# LCL_sch.net
KiCad netlist of a schematic drawn in Altium Designer
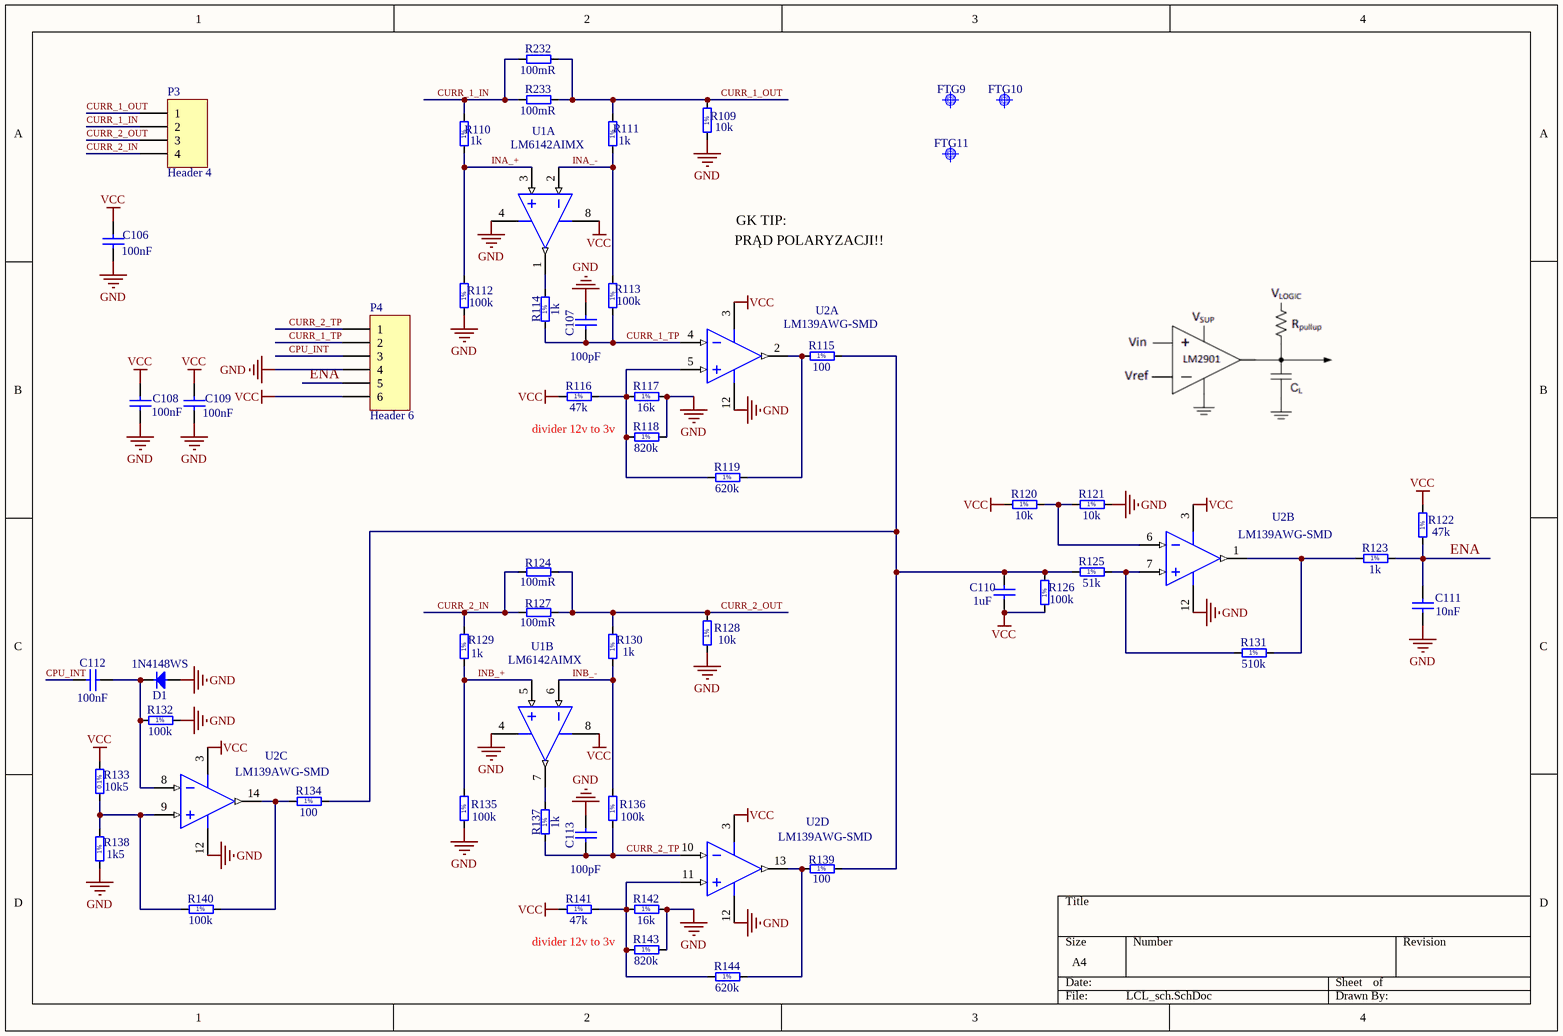
[diagram p0: LCL_sch.SchDoc]

(export (version "E")
  (design (tool "Eeschema 10.0.6"))
  (components
    (comp (ref "C106")
      (value "100nF")
      (footprint "CAPC1608X87N")
      (description "Non-polarised capacitor")
      (fields
        (field (name "PART NUMBER") "CC0603_100NF_50V_10%_X7R")
        (field (name "VOLTAGE") "50V")
        (field (name "AUTHOR") "CERN DEM JLC")
      )
      (libsource (lib "Capacitors") (part "Capacitor - non polarized"))
    )
    (comp (ref "C107")
      (value "100pF")
      (footprint "CAPC1608X87N")
      (description "Non-polarised capacitor")
      (fields
        (field (name "PART NUMBER") "CC0603_100PF_50V_10%_X7R")
        (field (name "VOLTAGE") "50V")
        (field (name "AUTHOR") "CERN DEM JLC")
      )
      (libsource (lib "Capacitors") (part "Capacitor - non polarized"))
    )
    (comp (ref "C108")
      (value "100nF")
      (footprint "CAPC1608X87N")
      (description "Non-polarised capacitor")
      (fields
        (field (name "PART NUMBER") "CC0603_100NF_50V_10%_X7R")
        (field (name "VOLTAGE") "50V")
        (field (name "AUTHOR") "CERN DEM JLC")
      )
      (libsource (lib "Capacitors") (part "Capacitor - non polarized"))
    )
    (comp (ref "C109")
      (value "100nF")
      (footprint "CAPC1608X87N")
      (description "Non-polarised capacitor")
      (fields
        (field (name "PART NUMBER") "CC0603_100NF_50V_10%_X7R")
        (field (name "VOLTAGE") "50V")
        (field (name "AUTHOR") "CERN DEM JLC")
      )
      (libsource (lib "Capacitors") (part "Capacitor - non polarized"))
    )
    (comp (ref "C110")
      (value "1uF")
      (footprint "CAPC1608X87N")
      (description "Non-polarised capacitor")
      (fields
        (field (name "PART NUMBER") "CC0603_1UF_25V_10%_X7R")
        (field (name "VOLTAGE") "25V")
        (field (name "AUTHOR") "CERN DEM JLC")
      )
      (libsource (lib "Capacitors") (part "Capacitor - non polarized"))
    )
    (comp (ref "C111")
      (value "10nF")
      (footprint "CAPC1608X87N")
      (description "Non-polarised capacitor")
      (fields
        (field (name "PART NUMBER") "CC0603_10NF_50V_10%_X7R")
        (field (name "VOLTAGE") "50V")
        (field (name "AUTHOR") "CERN DEM JLC")
      )
      (libsource (lib "Capacitors") (part "Capacitor - non polarized"))
    )
    (comp (ref "C112")
      (value "100nF")
      (footprint "CAPC1608X87N")
      (description "Non-polarised capacitor")
      (fields
        (field (name "PART NUMBER") "CC0603_100NF_50V_10%_X7R")
        (field (name "VOLTAGE") "50V")
        (field (name "AUTHOR") "CERN DEM JLC")
      )
      (libsource (lib "Capacitors") (part "Capacitor - non polarized"))
    )
    (comp (ref "C113")
      (value "100pF")
      (footprint "CAPC1608X87N")
      (description "Non-polarised capacitor")
      (fields
        (field (name "PART NUMBER") "CC0603_100PF_50V_10%_X7R")
        (field (name "VOLTAGE") "50V")
        (field (name "AUTHOR") "CERN DEM JLC")
      )
      (libsource (lib "Capacitors") (part "Capacitor - non polarized"))
    )
    (comp (ref "D1")
      (value "1N4148WS")
      (footprint "SODFL2512X100N")
      (description "Diode")
      (fields
        (field (name "VOLTAGE") "75V")
        (field (name "POWER") "150mA")
        (field (name "AUTHOR") "CERN DEM JLC")
      )
      (libsource (lib "ICs And Semiconductors") (part "Diode"))
    )
    (comp (ref "FTG9")
      (value "Use only in PCB")
      (footprint "FIDUCIAL_TOP_C100-200")
      (description "Fiducial Target")
      (fields (field (name "PART NUMBER") "FIDUCIAL_TARGET_C100-200") (field (name "AUTHOR") "CERN DEM JLC"))
      (libsource (lib "Eletro-mechanical") (part "Fiducial Target"))
    )
    (comp (ref "FTG10")
      (value "Use only in PCB")
      (footprint "FIDUCIAL_TOP_C100-200")
      (description "Fiducial Target")
      (fields (field (name "PART NUMBER") "FIDUCIAL_TARGET_C100-200") (field (name "AUTHOR") "CERN DEM JLC"))
      (libsource (lib "Eletro-mechanical") (part "Fiducial Target"))
    )
    (comp (ref "FTG11")
      (value "Use only in PCB")
      (footprint "FIDUCIAL_TOP_C100-200")
      (description "Fiducial Target")
      (fields (field (name "PART NUMBER") "FIDUCIAL_TARGET_C100-200") (field (name "AUTHOR") "CERN DEM JLC"))
      (libsource (lib "Eletro-mechanical") (part "Fiducial Target"))
    )
    (comp (ref "P3")
      (value "Header 4")
      (footprint "1x4 Header 2mm male")
      (description "Header, 4-Pin")
      (fields (field (name "PUBLISHER") "Altium Limited"))
      (libsource (lib "Connectors-headers") (part "Header 4"))
    )
    (comp (ref "P4")
      (value "Header 6")
      (footprint "2x3 Header 2mm male")
      (description "Header, 6-Pin")
      (fields (field (name "PUBLISHER") "Altium Limited"))
      (libsource (lib "Connectors-headers") (part "Header 6"))
    )
    (comp (ref "R109")
      (value "10k")
      (footprint "RESC1608X55N")
      (description "Resistor - 1%")
      (fields
        (field (name "PART NUMBER") "R0603_10K_1%_0.1W_100PPM")
        (field (name "POWER") "0.1W")
        (field (name "AUTHOR") "CERN DEM JLC")
      )
      (libsource (lib "Resistors") (part "Resistor - 1%"))
    )
    (comp (ref "R110")
      (value "1k")
      (footprint "RESC1608X55N")
      (description "Resistor - 1%")
      (fields
        (field (name "PART NUMBER") "R0603_1K_1%_0.1W_100PPM")
        (field (name "POWER") "0.1W")
        (field (name "AUTHOR") "CERN DEM JLC")
      )
      (libsource (lib "Resistors") (part "Resistor - 1%"))
    )
    (comp (ref "R111")
      (value "1k")
      (footprint "RESC1608X55N")
      (description "Resistor - 1%")
      (fields
        (field (name "PART NUMBER") "R0603_1K_1%_0.1W_100PPM")
        (field (name "POWER") "0.1W")
        (field (name "AUTHOR") "CERN DEM JLC")
      )
      (libsource (lib "Resistors") (part "Resistor - 1%"))
    )
    (comp (ref "R112")
      (value "100k")
      (footprint "RESC1608X55N")
      (description "Resistor - 1%")
      (fields
        (field (name "PART NUMBER") "R0603_100K_1%_0.1W_100PPM")
        (field (name "POWER") "0.1W")
        (field (name "AUTHOR") "CERN DEM JLC")
      )
      (libsource (lib "Resistors") (part "Resistor - 1%"))
    )
    (comp (ref "R113")
      (value "100k")
      (footprint "RESC1608X55N")
      (description "Resistor - 1%")
      (fields
        (field (name "PART NUMBER") "R0603_100K_1%_0.1W_100PPM")
        (field (name "POWER") "0.1W")
        (field (name "AUTHOR") "CERN DEM JLC")
      )
      (libsource (lib "Resistors") (part "Resistor - 1%"))
    )
    (comp (ref "R114")
      (value "1k")
      (footprint "RESC1608X55N")
      (description "Resistor - 1%")
      (fields
        (field (name "PART NUMBER") "R0603_1K_1%_0.1W_100PPM")
        (field (name "POWER") "0.1W")
        (field (name "AUTHOR") "CERN DEM JLC")
      )
      (libsource (lib "Resistors") (part "Resistor - 1%"))
    )
    (comp (ref "R115")
      (value "100")
      (footprint "RESC1608X55N")
      (description "Resistor - 1%")
      (fields
        (field (name "PART NUMBER") "R0603_100R_1%_0.1W_100PPM")
        (field (name "POWER") "0.1W")
        (field (name "AUTHOR") "CERN DEM JLC")
      )
      (libsource (lib "Resistors") (part "Resistor - 1%"))
    )
    (comp (ref "R116")
      (value "47k")
      (footprint "RESC1608X55N")
      (description "Resistor - 1%")
      (fields
        (field (name "PART NUMBER") "R0603_47K_1%_0.1W_100PPM")
        (field (name "POWER") "0.1W")
        (field (name "AUTHOR") "CERN DEM JLC")
      )
      (libsource (lib "Resistors") (part "Resistor - 1%"))
    )
    (comp (ref "R117")
      (value "16k")
      (footprint "RESC1608X55N")
      (description "Resistor - 1%")
      (fields
        (field (name "PART NUMBER") "R0603_16K_1%_0.1W_100PPM")
        (field (name "POWER") "0.1W")
        (field (name "AUTHOR") "CERN DEM JLC")
      )
      (libsource (lib "Resistors") (part "Resistor - 1%"))
    )
    (comp (ref "R118")
      (value "820k")
      (footprint "RESC1608X55N")
      (description "Resistor - 1%")
      (fields
        (field (name "PART NUMBER") "R0603_820K_1%_0.1W_100PPM")
        (field (name "POWER") "0.1W")
        (field (name "AUTHOR") "CERN DEM JLC")
      )
      (libsource (lib "Resistors") (part "Resistor - 1%"))
    )
    (comp (ref "R119")
      (value "620k")
      (footprint "RESC1608X55N")
      (description "Resistor - 1%")
      (fields
        (field (name "PART NUMBER") "R0603_620K_1%_0.1W_100PPM")
        (field (name "POWER") "0.1W")
        (field (name "AUTHOR") "CERN DEM JLC")
      )
      (libsource (lib "Resistors") (part "Resistor - 1%"))
    )
    (comp (ref "R120")
      (value "10k")
      (footprint "RESC1608X55N")
      (description "Resistor - 1%")
      (fields
        (field (name "PART NUMBER") "R0603_10K_1%_0.1W_100PPM")
        (field (name "POWER") "0.1W")
        (field (name "AUTHOR") "CERN DEM JLC")
      )
      (libsource (lib "Resistors") (part "Resistor - 1%"))
    )
    (comp (ref "R121")
      (value "10k")
      (footprint "RESC1608X55N")
      (description "Resistor - 1%")
      (fields
        (field (name "PART NUMBER") "R0603_10K_1%_0.1W_100PPM")
        (field (name "POWER") "0.1W")
        (field (name "AUTHOR") "CERN DEM JLC")
      )
      (libsource (lib "Resistors") (part "Resistor - 1%"))
    )
    (comp (ref "R122")
      (value "47k")
      (footprint "RESC1608X55N")
      (description "Resistor - 1%")
      (fields
        (field (name "PART NUMBER") "R0603_47K_1%_0.1W_100PPM")
        (field (name "POWER") "0.1W")
        (field (name "AUTHOR") "CERN DEM JLC")
      )
      (libsource (lib "Resistors") (part "Resistor - 1%"))
    )
    (comp (ref "R123")
      (value "1k")
      (footprint "RESC1608X55N")
      (description "Resistor - 1%")
      (fields
        (field (name "PART NUMBER") "R0603_1K_1%_0.1W_100PPM")
        (field (name "POWER") "0.1W")
        (field (name "AUTHOR") "CERN DEM JLC")
      )
      (libsource (lib "Resistors") (part "Resistor - 1%"))
    )
    (comp (ref "R124")
      (value "100mR")
      (footprint "RESC1608X55N")
      (description "Resistor")
      (fields
        (field (name "PART NUMBER") "100mR 0603")
        (field (name "MANUFACTURER") "GENERIC")
        (field (name "AUTHOR") "CERN DEM JLC")
      )
      (libsource (lib "Resistors") (part "Resistor"))
    )
    (comp (ref "R125")
      (value "51k")
      (footprint "RESC1608X55N")
      (description "Resistor - 1%")
      (fields
        (field (name "PART NUMBER") "R0603_51K_1%_0.1W_100PPM")
        (field (name "POWER") "0.1W")
        (field (name "AUTHOR") "CERN DEM JLC")
      )
      (libsource (lib "Resistors") (part "Resistor - 1%"))
    )
    (comp (ref "R126")
      (value "100k")
      (footprint "RESC1608X55N")
      (description "Resistor - 1%")
      (fields
        (field (name "PART NUMBER") "R0603_100K_1%_0.1W_100PPM")
        (field (name "POWER") "0.1W")
        (field (name "AUTHOR") "CERN DEM JLC")
      )
      (libsource (lib "Resistors") (part "Resistor - 1%"))
    )
    (comp (ref "R127")
      (value "100mR")
      (footprint "RESC1608X55N")
      (description "Resistor")
      (fields
        (field (name "PART NUMBER") "100mR 0603")
        (field (name "MANUFACTURER") "GENERIC")
        (field (name "AUTHOR") "CERN DEM JLC")
      )
      (libsource (lib "Resistors") (part "Resistor"))
    )
    (comp (ref "R128")
      (value "10k")
      (footprint "RESC1608X55N")
      (description "Resistor - 1%")
      (fields
        (field (name "PART NUMBER") "R0603_10K_1%_0.1W_100PPM")
        (field (name "POWER") "0.1W")
        (field (name "AUTHOR") "CERN DEM JLC")
      )
      (libsource (lib "Resistors") (part "Resistor - 1%"))
    )
    (comp (ref "R129")
      (value "1k")
      (footprint "RESC1608X55N")
      (description "Resistor - 1%")
      (fields
        (field (name "PART NUMBER") "R0603_1K_1%_0.1W_100PPM")
        (field (name "POWER") "0.1W")
        (field (name "AUTHOR") "CERN DEM JLC")
      )
      (libsource (lib "Resistors") (part "Resistor - 1%"))
    )
    (comp (ref "R130")
      (value "1k")
      (footprint "RESC1608X55N")
      (description "Resistor - 1%")
      (fields
        (field (name "PART NUMBER") "R0603_1K_1%_0.1W_100PPM")
        (field (name "POWER") "0.1W")
        (field (name "AUTHOR") "CERN DEM JLC")
      )
      (libsource (lib "Resistors") (part "Resistor - 1%"))
    )
    (comp (ref "R131")
      (value "510k")
      (footprint "RESC1608X55N")
      (description "Resistor - 1%")
      (fields
        (field (name "PART NUMBER") "R0603_510K_1%_0.1W_100PPM")
        (field (name "POWER") "0.1W")
        (field (name "AUTHOR") "CERN DEM JLC")
      )
      (libsource (lib "Resistors") (part "Resistor - 1%"))
    )
    (comp (ref "R132")
      (value "100k")
      (footprint "RESC1608X55N")
      (description "Resistor - 1%")
      (fields
        (field (name "PART NUMBER") "R0603_100K_1%_0.1W_100PPM")
        (field (name "POWER") "0.1W")
        (field (name "AUTHOR") "CERN DEM JLC")
      )
      (libsource (lib "Resistors") (part "Resistor - 1%"))
    )
    (comp (ref "R133")
      (value "10k5")
      (footprint "RESC1608X55N")
      (description "Resistor - 0.1%")
      (fields
        (field (name "PART NUMBER") "R0603_10K5_0.1%_0.063W_10PPM")
        (field (name "POWER") "0.063W")
        (field (name "AUTHOR") "CERN DEM JLC")
      )
      (libsource (lib "Resistors") (part "Resistor - 0.1%"))
    )
    (comp (ref "R134")
      (value "100")
      (footprint "RESC1608X55N")
      (description "Resistor - 1%")
      (fields
        (field (name "PART NUMBER") "R0603_100R_1%_0.1W_100PPM")
        (field (name "POWER") "0.1W")
        (field (name "AUTHOR") "CERN DEM JLC")
      )
      (libsource (lib "Resistors") (part "Resistor - 1%"))
    )
    (comp (ref "R135")
      (value "100k")
      (footprint "RESC1608X55N")
      (description "Resistor - 1%")
      (fields
        (field (name "PART NUMBER") "R0603_100K_1%_0.1W_100PPM")
        (field (name "POWER") "0.1W")
        (field (name "AUTHOR") "CERN DEM JLC")
      )
      (libsource (lib "Resistors") (part "Resistor - 1%"))
    )
    (comp (ref "R136")
      (value "100k")
      (footprint "RESC1608X55N")
      (description "Resistor - 1%")
      (fields
        (field (name "PART NUMBER") "R0603_100K_1%_0.1W_100PPM")
        (field (name "POWER") "0.1W")
        (field (name "AUTHOR") "CERN DEM JLC")
      )
      (libsource (lib "Resistors") (part "Resistor - 1%"))
    )
    (comp (ref "R137")
      (value "1k")
      (footprint "RESC1608X55N")
      (description "Resistor - 1%")
      (fields
        (field (name "PART NUMBER") "R0603_1K_1%_0.1W_100PPM")
        (field (name "POWER") "0.1W")
        (field (name "AUTHOR") "CERN DEM JLC")
      )
      (libsource (lib "Resistors") (part "Resistor - 1%"))
    )
    (comp (ref "R138")
      (value "1k5")
      (footprint "RESC1608X55N")
      (description "Resistor - 1%")
      (fields
        (field (name "PART NUMBER") "R0603_1K5_1%_0.1W_100PPM")
        (field (name "POWER") "0.1W")
        (field (name "AUTHOR") "CERN DEM JLC")
      )
      (libsource (lib "Resistors") (part "Resistor - 1%"))
    )
    (comp (ref "R139")
      (value "100")
      (footprint "RESC1608X55N")
      (description "Resistor - 1%")
      (fields
        (field (name "PART NUMBER") "R0603_100R_1%_0.1W_100PPM")
        (field (name "POWER") "0.1W")
        (field (name "AUTHOR") "CERN DEM JLC")
      )
      (libsource (lib "Resistors") (part "Resistor - 1%"))
    )
    (comp (ref "R140")
      (value "100k")
      (footprint "RESC1608X55N")
      (description "Resistor - 1%")
      (fields
        (field (name "PART NUMBER") "R0603_100K_1%_0.1W_100PPM")
        (field (name "POWER") "0.1W")
        (field (name "AUTHOR") "CERN DEM JLC")
      )
      (libsource (lib "Resistors") (part "Resistor - 1%"))
    )
    (comp (ref "R141")
      (value "47k")
      (footprint "RESC1608X55N")
      (description "Resistor - 1%")
      (fields
        (field (name "PART NUMBER") "R0603_47K_1%_0.1W_100PPM")
        (field (name "POWER") "0.1W")
        (field (name "AUTHOR") "CERN DEM JLC")
      )
      (libsource (lib "Resistors") (part "Resistor - 1%"))
    )
    (comp (ref "R142")
      (value "16k")
      (footprint "RESC1608X55N")
      (description "Resistor - 1%")
      (fields
        (field (name "PART NUMBER") "R0603_16K_1%_0.1W_100PPM")
        (field (name "POWER") "0.1W")
        (field (name "AUTHOR") "CERN DEM JLC")
      )
      (libsource (lib "Resistors") (part "Resistor - 1%"))
    )
    (comp (ref "R143")
      (value "820k")
      (footprint "RESC1608X55N")
      (description "Resistor - 1%")
      (fields
        (field (name "PART NUMBER") "R0603_820K_1%_0.1W_100PPM")
        (field (name "POWER") "0.1W")
        (field (name "AUTHOR") "CERN DEM JLC")
      )
      (libsource (lib "Resistors") (part "Resistor - 1%"))
    )
    (comp (ref "R144")
      (value "620k")
      (footprint "RESC1608X55N")
      (description "Resistor - 1%")
      (fields
        (field (name "PART NUMBER") "R0603_620K_1%_0.1W_100PPM")
        (field (name "POWER") "0.1W")
        (field (name "AUTHOR") "CERN DEM JLC")
      )
      (libsource (lib "Resistors") (part "Resistor - 1%"))
    )
    (comp (ref "R232")
      (value "100mR")
      (footprint "RESC1608X55N")
      (description "Resistor")
      (fields
        (field (name "PART NUMBER") "100mR 0603")
        (field (name "MANUFACTURER") "GENERIC")
        (field (name "AUTHOR") "CERN DEM JLC")
      )
      (libsource (lib "Resistors") (part "Resistor"))
    )
    (comp (ref "R233")
      (value "100mR")
      (footprint "RESC1608X55N")
      (description "Resistor")
      (fields
        (field (name "PART NUMBER") "100mR 0603")
        (field (name "MANUFACTURER") "GENERIC")
        (field (name "AUTHOR") "CERN DEM JLC")
      )
      (libsource (lib "Resistors") (part "Resistor"))
    )
    (comp (ref "U1")
      (value "LM6142AIMX")
      (footprint "M08A_N")
      (description "Dual High Speed/Low Power 17 MHz Rail-to-Rail I/O Operational Amplifier, 8-pin Narrow SOIC")
      (fields (field (name "MANUFACTURER") "National Semiconductor"))
      (libsource (lib "National Semiconductor Amplifier") (part "LM6142AIMX"))
    )
    (comp (ref "U2")
      (value "LM139AWG-SMD")
      (footprint "WG14A_N")
      (description "Low Power Low Offset Voltage Quad Comparator, 14-pin CerPACK")
      (fields (field (name "MANUFACTURER") "National Semiconductor"))
      (libsource (lib "National Semiconductor Amplifier") (part "LM139AWG-SMD"))
    )
  )
  (nets
    (net (code "1") (name "/CPU_INT") (class "Default")
      (node (ref "C112") (pin "1") (pinfunction "1_1") (pintype "passive"))
      (node (ref "P4") (pin "3") (pinfunction "3_3") (pintype "passive"))
    )
    (net (code "2") (name "/CURR_1_IN") (class "Default")
      (node (ref "P3") (pin "2") (pinfunction "2_2") (pintype "passive"))
      (node (ref "R110") (pin "2") (pinfunction "2_2") (pintype "passive"))
      (node (ref "R232") (pin "1") (pinfunction "1_1") (pintype "passive"))
      (node (ref "R233") (pin "1") (pinfunction "1_1") (pintype "passive"))
    )
    (net (code "3") (name "/CURR_1_OUT") (class "Default")
      (node (ref "P3") (pin "1") (pinfunction "1_1") (pintype "passive"))
      (node (ref "R109") (pin "2") (pinfunction "2_2") (pintype "passive"))
      (node (ref "R111") (pin "2") (pinfunction "2_2") (pintype "passive"))
      (node (ref "R232") (pin "2") (pinfunction "2_2") (pintype "passive"))
      (node (ref "R233") (pin "2") (pinfunction "2_2") (pintype "passive"))
    )
    (net (code "4") (name "/CURR_1_TP") (class "Default")
      (node (ref "C107") (pin "1") (pinfunction "1_1") (pintype "passive"))
      (node (ref "P4") (pin "2") (pinfunction "2_2") (pintype "passive"))
      (node (ref "R113") (pin "1") (pinfunction "1_1") (pintype "passive"))
      (node (ref "R114") (pin "1") (pinfunction "1_1") (pintype "passive"))
      (node (ref "U2") (pin "4") (pinfunction "IN1-_4") (pintype "input"))
    )
    (net (code "5") (name "/CURR_2_IN") (class "Default")
      (node (ref "P3") (pin "4") (pinfunction "4_4") (pintype "passive"))
      (node (ref "R124") (pin "1") (pinfunction "1_1") (pintype "passive"))
      (node (ref "R127") (pin "1") (pinfunction "1_1") (pintype "passive"))
      (node (ref "R129") (pin "2") (pinfunction "2_2") (pintype "passive"))
    )
    (net (code "6") (name "/CURR_2_OUT") (class "Default")
      (node (ref "P3") (pin "3") (pinfunction "3_3") (pintype "passive"))
      (node (ref "R124") (pin "2") (pinfunction "2_2") (pintype "passive"))
      (node (ref "R127") (pin "2") (pinfunction "2_2") (pintype "passive"))
      (node (ref "R128") (pin "2") (pinfunction "2_2") (pintype "passive"))
      (node (ref "R130") (pin "2") (pinfunction "2_2") (pintype "passive"))
    )
    (net (code "7") (name "/CURR_2_TP") (class "Default")
      (node (ref "C113") (pin "1") (pinfunction "1_1") (pintype "passive"))
      (node (ref "P4") (pin "1") (pinfunction "1_1") (pintype "passive"))
      (node (ref "R136") (pin "1") (pinfunction "1_1") (pintype "passive"))
      (node (ref "R137") (pin "1") (pinfunction "1_1") (pintype "passive"))
      (node (ref "U2") (pin "10") (pinfunction "IN4-_10") (pintype "input"))
    )
    (net (code "8") (name "/ENA") (class "Default")
      (node (ref "C111") (pin "2") (pinfunction "2_2") (pintype "passive"))
      (node (ref "P4") (pin "5") (pinfunction "5_5") (pintype "passive"))
      (node (ref "R122") (pin "1") (pinfunction "1_1") (pintype "passive"))
      (node (ref "R123") (pin "2") (pinfunction "2_2") (pintype "passive"))
    )
    (net (code "9") (name "/INA_+") (class "Default")
      (node (ref "R110") (pin "1") (pinfunction "1_1") (pintype "passive"))
      (node (ref "R112") (pin "2") (pinfunction "2_2") (pintype "passive"))
      (node (ref "U1") (pin "3") (pinfunction "INA+_3") (pintype "input"))
    )
    (net (code "10") (name "/INA_-") (class "Default")
      (node (ref "R111") (pin "1") (pinfunction "1_1") (pintype "passive"))
      (node (ref "R113") (pin "2") (pinfunction "2_2") (pintype "passive"))
      (node (ref "U1") (pin "2") (pinfunction "INA-_2") (pintype "input"))
    )
    (net (code "11") (name "/INB_+") (class "Default")
      (node (ref "R129") (pin "1") (pinfunction "1_1") (pintype "passive"))
      (node (ref "R135") (pin "2") (pinfunction "2_2") (pintype "passive"))
      (node (ref "U1") (pin "5") (pinfunction "INB+_5") (pintype "input"))
    )
    (net (code "12") (name "/INB_-") (class "Default")
      (node (ref "R130") (pin "1") (pinfunction "1_1") (pintype "passive"))
      (node (ref "R136") (pin "2") (pinfunction "2_2") (pintype "passive"))
      (node (ref "U1") (pin "6") (pinfunction "INB-_6") (pintype "input"))
    )
    (net (code "13") (name "GND") (class "Default")
      (node (ref "C106") (pin "1") (pinfunction "1_1") (pintype "passive"))
      (node (ref "C107") (pin "2") (pinfunction "2_2") (pintype "passive"))
      (node (ref "C108") (pin "1") (pinfunction "1_1") (pintype "passive"))
      (node (ref "C109") (pin "1") (pinfunction "1_1") (pintype "passive"))
      (node (ref "C111") (pin "1") (pinfunction "1_1") (pintype "passive"))
      (node (ref "C113") (pin "2") (pinfunction "2_2") (pintype "passive"))
      (node (ref "D1") (pin "2") (pinfunction "A_2") (pintype "passive"))
      (node (ref "P4") (pin "4") (pinfunction "4_4") (pintype "passive"))
      (node (ref "R109") (pin "1") (pinfunction "1_1") (pintype "passive"))
      (node (ref "R112") (pin "1") (pinfunction "1_1") (pintype "passive"))
      (node (ref "R117") (pin "2") (pinfunction "2_2") (pintype "passive"))
      (node (ref "R118") (pin "2") (pinfunction "2_2") (pintype "passive"))
      (node (ref "R121") (pin "2") (pinfunction "2_2") (pintype "passive"))
      (node (ref "R128") (pin "1") (pinfunction "1_1") (pintype "passive"))
      (node (ref "R132") (pin "2") (pinfunction "2_2") (pintype "passive"))
      (node (ref "R135") (pin "1") (pinfunction "1_1") (pintype "passive"))
      (node (ref "R138") (pin "1") (pinfunction "1_1") (pintype "passive"))
      (node (ref "R142") (pin "2") (pinfunction "2_2") (pintype "passive"))
      (node (ref "R143") (pin "2") (pinfunction "2_2") (pintype "passive"))
      (node (ref "U1") (pin "4") (pinfunction "V-_4") (pintype "power_in"))
      (node (ref "U2") (pin "12") (pinfunction "GND_12") (pintype "power_in"))
    )
    (net (code "14") (name "Net-(C110-Pad2)") (class "Default")
      (node (ref "C110") (pin "2") (pinfunction "2_2") (pintype "passive"))
      (node (ref "R115") (pin "2") (pinfunction "2_2") (pintype "passive"))
      (node (ref "R125") (pin "1") (pinfunction "1_1") (pintype "passive"))
      (node (ref "R126") (pin "2") (pinfunction "2_2") (pintype "passive"))
      (node (ref "R134") (pin "2") (pinfunction "2_2") (pintype "passive"))
      (node (ref "R139") (pin "2") (pinfunction "2_2") (pintype "passive"))
    )
    (net (code "15") (name "Net-(D1-C)") (class "Default")
      (node (ref "C112") (pin "2") (pinfunction "2_2") (pintype "passive"))
      (node (ref "D1") (pin "1") (pinfunction "C_1") (pintype "passive"))
      (node (ref "R132") (pin "1") (pinfunction "1_1") (pintype "passive"))
      (node (ref "U2") (pin "8") (pinfunction "IN3-_8") (pintype "input"))
    )
    (net (code "16") (name "Net-(U1A-OUTA)") (class "Default")
      (node (ref "R114") (pin "2") (pinfunction "2_2") (pintype "passive"))
      (node (ref "U1") (pin "1") (pinfunction "OUTA_1") (pintype "output"))
    )
    (net (code "17") (name "Net-(U1B-OUTB)") (class "Default")
      (node (ref "R137") (pin "2") (pinfunction "2_2") (pintype "passive"))
      (node (ref "U1") (pin "7") (pinfunction "OUTB_7") (pintype "output"))
    )
    (net (code "18") (name "Net-(U2A-IN1+)") (class "Default")
      (node (ref "R116") (pin "2") (pinfunction "2_2") (pintype "passive"))
      (node (ref "R117") (pin "1") (pinfunction "1_1") (pintype "passive"))
      (node (ref "R118") (pin "1") (pinfunction "1_1") (pintype "passive"))
      (node (ref "R119") (pin "1") (pinfunction "1_1") (pintype "passive"))
      (node (ref "U2") (pin "5") (pinfunction "IN1+_5") (pintype "input"))
    )
    (net (code "19") (name "Net-(U2A-OUT1)") (class "Default")
      (node (ref "R115") (pin "1") (pinfunction "1_1") (pintype "passive"))
      (node (ref "R119") (pin "2") (pinfunction "2_2") (pintype "passive"))
      (node (ref "U2") (pin "2") (pinfunction "OUT1_2") (pintype "output"))
    )
    (net (code "20") (name "Net-(U2B-IN2+)") (class "Default")
      (node (ref "R125") (pin "2") (pinfunction "2_2") (pintype "passive"))
      (node (ref "R131") (pin "1") (pinfunction "1_1") (pintype "passive"))
      (node (ref "U2") (pin "7") (pinfunction "IN2+_7") (pintype "input"))
    )
    (net (code "21") (name "Net-(U2B-IN2-)") (class "Default")
      (node (ref "R120") (pin "2") (pinfunction "2_2") (pintype "passive"))
      (node (ref "R121") (pin "1") (pinfunction "1_1") (pintype "passive"))
      (node (ref "U2") (pin "6") (pinfunction "IN2-_6") (pintype "input"))
    )
    (net (code "22") (name "Net-(U2B-OUT2)") (class "Default")
      (node (ref "R123") (pin "1") (pinfunction "1_1") (pintype "passive"))
      (node (ref "R131") (pin "2") (pinfunction "2_2") (pintype "passive"))
      (node (ref "U2") (pin "1") (pinfunction "OUT2_1") (pintype "output"))
    )
    (net (code "23") (name "Net-(U2C-IN3+)") (class "Default")
      (node (ref "R133") (pin "1") (pinfunction "1_1") (pintype "passive"))
      (node (ref "R138") (pin "2") (pinfunction "2_2") (pintype "passive"))
      (node (ref "R140") (pin "1") (pinfunction "1_1") (pintype "passive"))
      (node (ref "U2") (pin "9") (pinfunction "IN3+_9") (pintype "input"))
    )
    (net (code "24") (name "Net-(U2C-OUT3)") (class "Default")
      (node (ref "R134") (pin "1") (pinfunction "1_1") (pintype "passive"))
      (node (ref "R140") (pin "2") (pinfunction "2_2") (pintype "passive"))
      (node (ref "U2") (pin "14") (pinfunction "OUT3_14") (pintype "output"))
    )
    (net (code "25") (name "Net-(U2D-IN4+)") (class "Default")
      (node (ref "R141") (pin "2") (pinfunction "2_2") (pintype "passive"))
      (node (ref "R142") (pin "1") (pinfunction "1_1") (pintype "passive"))
      (node (ref "R143") (pin "1") (pinfunction "1_1") (pintype "passive"))
      (node (ref "R144") (pin "1") (pinfunction "1_1") (pintype "passive"))
      (node (ref "U2") (pin "11") (pinfunction "IN4+_11") (pintype "input"))
    )
    (net (code "26") (name "Net-(U2D-OUT4)") (class "Default")
      (node (ref "R139") (pin "1") (pinfunction "1_1") (pintype "passive"))
      (node (ref "R144") (pin "2") (pinfunction "2_2") (pintype "passive"))
      (node (ref "U2") (pin "13") (pinfunction "OUT4_13") (pintype "output"))
    )
    (net (code "27") (name "VCC") (class "Default")
      (node (ref "C106") (pin "2") (pinfunction "2_2") (pintype "passive"))
      (node (ref "C108") (pin "2") (pinfunction "2_2") (pintype "passive"))
      (node (ref "C109") (pin "2") (pinfunction "2_2") (pintype "passive"))
      (node (ref "C110") (pin "1") (pinfunction "1_1") (pintype "passive"))
      (node (ref "P4") (pin "6") (pinfunction "6_6") (pintype "passive"))
      (node (ref "R116") (pin "1") (pinfunction "1_1") (pintype "passive"))
      (node (ref "R120") (pin "1") (pinfunction "1_1") (pintype "passive"))
      (node (ref "R122") (pin "2") (pinfunction "2_2") (pintype "passive"))
      (node (ref "R126") (pin "1") (pinfunction "1_1") (pintype "passive"))
      (node (ref "R133") (pin "2") (pinfunction "2_2") (pintype "passive"))
      (node (ref "R141") (pin "1") (pinfunction "1_1") (pintype "passive"))
      (node (ref "U1") (pin "8") (pinfunction "V+_8") (pintype "power_in"))
      (node (ref "U2") (pin "3") (pinfunction "V+_3") (pintype "power_in"))
    )
  )
)
